# pots-board.net
KiCad netlist of a schematic drawn in EAGLE
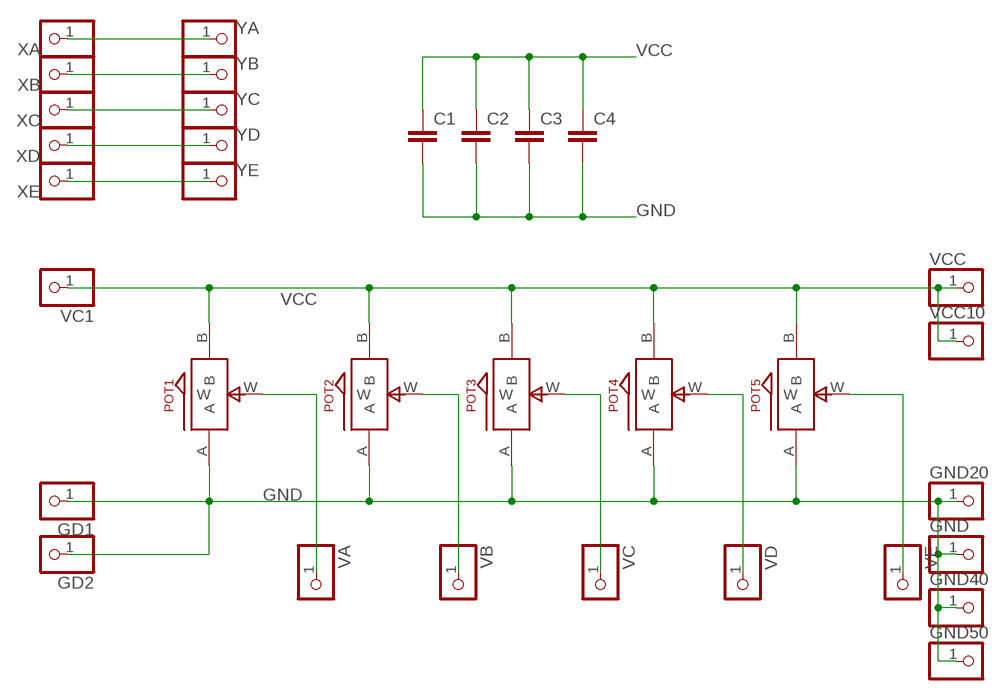
[diagram p0: schematic, sheet 1]

(export (version "E")
  (design (tool "Eeschema 10.0.6"))
  (components
    (comp (ref "C1")
      (value "C-EUC0805")
      (footprint "eagle-import:C0805")
      (libsource (lib "eagle-import") (part "C-EUC0805"))
    )
    (comp (ref "C2")
      (value "C-EUC0805")
      (footprint "eagle-import:C0805")
      (libsource (lib "eagle-import") (part "C-EUC0805"))
    )
    (comp (ref "C3")
      (value "C-EUC0805")
      (footprint "eagle-import:C0805")
      (libsource (lib "eagle-import") (part "C-EUC0805"))
    )
    (comp (ref "C4")
      (value "C-EUC0805")
      (footprint "eagle-import:C0805")
      (libsource (lib "eagle-import") (part "C-EUC0805"))
    )
    (comp (ref "GD1")
      (value "PINHD-1X1")
      (footprint "eagle-import:1X01")
      (libsource (lib "eagle-import") (part "PINHD-1X1"))
    )
    (comp (ref "GD2")
      (value "PINHD-1X1")
      (footprint "eagle-import:1X01")
      (libsource (lib "eagle-import") (part "PINHD-1X1"))
    )
    (comp (ref "GND")
      (value "PINHD-1X1")
      (footprint "eagle-import:1X01")
      (libsource (lib "eagle-import") (part "PINHD-1X1"))
    )
    (comp (ref "GND20")
      (value "PINHD-1X1")
      (footprint "eagle-import:1X01")
      (libsource (lib "eagle-import") (part "PINHD-1X1"))
    )
    (comp (ref "GND40")
      (value "PINHD-1X1")
      (footprint "eagle-import:1X01")
      (libsource (lib "eagle-import") (part "PINHD-1X1"))
    )
    (comp (ref "GND50")
      (value "PINHD-1X1")
      (footprint "eagle-import:1X01")
      (libsource (lib "eagle-import") (part "PINHD-1X1"))
    )
    (comp (ref "POT1")
      (value "ALPS_POT_SMALL")
      (footprint "eagle-import:SMALL_ALPS_POT")
      (libsource (lib "eagle-import") (part "ALPS_POT_SMALL"))
    )
    (comp (ref "POT2")
      (value "ALPS_POT_SMALL")
      (footprint "eagle-import:SMALL_ALPS_POT")
      (libsource (lib "eagle-import") (part "ALPS_POT_SMALL"))
    )
    (comp (ref "POT3")
      (value "ALPS_POT_SMALL")
      (footprint "eagle-import:SMALL_ALPS_POT")
      (libsource (lib "eagle-import") (part "ALPS_POT_SMALL"))
    )
    (comp (ref "POT4")
      (value "ALPS_POT_SMALL")
      (footprint "eagle-import:SMALL_ALPS_POT")
      (libsource (lib "eagle-import") (part "ALPS_POT_SMALL"))
    )
    (comp (ref "POT5")
      (value "ALPS_POT_SMALL")
      (footprint "eagle-import:SMALL_ALPS_POT")
      (libsource (lib "eagle-import") (part "ALPS_POT_SMALL"))
    )
    (comp (ref "VA")
      (value "PINHD-1X1")
      (footprint "eagle-import:1X01")
      (libsource (lib "eagle-import") (part "PINHD-1X1"))
    )
    (comp (ref "VB")
      (value "PINHD-1X1")
      (footprint "eagle-import:1X01")
      (libsource (lib "eagle-import") (part "PINHD-1X1"))
    )
    (comp (ref "VC")
      (value "PINHD-1X1")
      (footprint "eagle-import:1X01")
      (libsource (lib "eagle-import") (part "PINHD-1X1"))
    )
    (comp (ref "VC1")
      (value "PINHD-1X1")
      (footprint "eagle-import:1X01")
      (libsource (lib "eagle-import") (part "PINHD-1X1"))
    )
    (comp (ref "VCC")
      (value "PINHD-1X1")
      (footprint "eagle-import:1X01")
      (libsource (lib "eagle-import") (part "PINHD-1X1"))
    )
    (comp (ref "VCC10")
      (value "PINHD-1X1")
      (footprint "eagle-import:1X01")
      (libsource (lib "eagle-import") (part "PINHD-1X1"))
    )
    (comp (ref "VD")
      (value "PINHD-1X1")
      (footprint "eagle-import:1X01")
      (libsource (lib "eagle-import") (part "PINHD-1X1"))
    )
    (comp (ref "VE")
      (value "PINHD-1X1")
      (footprint "eagle-import:1X01")
      (libsource (lib "eagle-import") (part "PINHD-1X1"))
    )
    (comp (ref "XA")
      (value "PINHD-1X1")
      (footprint "eagle-import:1X01")
      (libsource (lib "eagle-import") (part "PINHD-1X1"))
    )
    (comp (ref "XB")
      (value "PINHD-1X1")
      (footprint "eagle-import:1X01")
      (libsource (lib "eagle-import") (part "PINHD-1X1"))
    )
    (comp (ref "XC")
      (value "PINHD-1X1")
      (footprint "eagle-import:1X01")
      (libsource (lib "eagle-import") (part "PINHD-1X1"))
    )
    (comp (ref "XD")
      (value "PINHD-1X1")
      (footprint "eagle-import:1X01")
      (libsource (lib "eagle-import") (part "PINHD-1X1"))
    )
    (comp (ref "XE")
      (value "PINHD-1X1")
      (footprint "eagle-import:1X01")
      (libsource (lib "eagle-import") (part "PINHD-1X1"))
    )
    (comp (ref "YA")
      (value "PINHD-1X1")
      (footprint "eagle-import:1X01")
      (libsource (lib "eagle-import") (part "PINHD-1X1"))
    )
    (comp (ref "YB")
      (value "PINHD-1X1")
      (footprint "eagle-import:1X01")
      (libsource (lib "eagle-import") (part "PINHD-1X1"))
    )
    (comp (ref "YC")
      (value "PINHD-1X1")
      (footprint "eagle-import:1X01")
      (libsource (lib "eagle-import") (part "PINHD-1X1"))
    )
    (comp (ref "YD")
      (value "PINHD-1X1")
      (footprint "eagle-import:1X01")
      (libsource (lib "eagle-import") (part "PINHD-1X1"))
    )
    (comp (ref "YE")
      (value "PINHD-1X1")
      (footprint "eagle-import:1X01")
      (libsource (lib "eagle-import") (part "PINHD-1X1"))
    )
  )
  (nets
    (net (code "1") (name "/GND") (class "Default")
      (node (ref "C1") (pin "2") (pinfunction "2_2") (pintype "passive"))
      (node (ref "C2") (pin "2") (pinfunction "2_2") (pintype "passive"))
      (node (ref "C3") (pin "2") (pinfunction "2_2") (pintype "passive"))
      (node (ref "C4") (pin "2") (pinfunction "2_2") (pintype "passive"))
      (node (ref "GD1") (pin "1") (pinfunction "1_1") (pintype "passive"))
      (node (ref "GD2") (pin "1") (pinfunction "1_1") (pintype "passive"))
      (node (ref "GND") (pin "1") (pinfunction "1_1") (pintype "passive"))
      (node (ref "GND20") (pin "1") (pinfunction "1_1") (pintype "passive"))
      (node (ref "GND40") (pin "1") (pinfunction "1_1") (pintype "passive"))
      (node (ref "GND50") (pin "1") (pinfunction "1_1") (pintype "passive"))
      (node (ref "POT1") (pin "A") (pinfunction "A_A") (pintype "bidirectional"))
      (node (ref "POT2") (pin "A") (pinfunction "A_A") (pintype "bidirectional"))
      (node (ref "POT3") (pin "A") (pinfunction "A_A") (pintype "bidirectional"))
      (node (ref "POT4") (pin "A") (pinfunction "A_A") (pintype "bidirectional"))
      (node (ref "POT5") (pin "A") (pinfunction "A_A") (pintype "bidirectional"))
    )
    (net (code "2") (name "/VCC") (class "Default")
      (node (ref "C1") (pin "1") (pinfunction "1_1") (pintype "passive"))
      (node (ref "C2") (pin "1") (pinfunction "1_1") (pintype "passive"))
      (node (ref "C3") (pin "1") (pinfunction "1_1") (pintype "passive"))
      (node (ref "C4") (pin "1") (pinfunction "1_1") (pintype "passive"))
      (node (ref "POT1") (pin "B") (pinfunction "B_B") (pintype "bidirectional"))
      (node (ref "POT2") (pin "B") (pinfunction "B_B") (pintype "bidirectional"))
      (node (ref "POT3") (pin "B") (pinfunction "B_B") (pintype "bidirectional"))
      (node (ref "POT4") (pin "B") (pinfunction "B_B") (pintype "bidirectional"))
      (node (ref "POT5") (pin "B") (pinfunction "B_B") (pintype "bidirectional"))
      (node (ref "VC1") (pin "1") (pinfunction "1_1") (pintype "passive"))
      (node (ref "VCC") (pin "1") (pinfunction "1_1") (pintype "passive"))
      (node (ref "VCC10") (pin "1") (pinfunction "1_1") (pintype "passive"))
    )
    (net (code "3") (name "Net-(POT1-PadW)") (class "Default")
      (node (ref "POT1") (pin "W") (pinfunction "W_W") (pintype "bidirectional"))
      (node (ref "VA") (pin "1") (pinfunction "1_1") (pintype "passive"))
    )
    (net (code "4") (name "Net-(POT2-PadW)") (class "Default")
      (node (ref "POT2") (pin "W") (pinfunction "W_W") (pintype "bidirectional"))
      (node (ref "VB") (pin "1") (pinfunction "1_1") (pintype "passive"))
    )
    (net (code "5") (name "Net-(POT3-PadW)") (class "Default")
      (node (ref "POT3") (pin "W") (pinfunction "W_W") (pintype "bidirectional"))
      (node (ref "VC") (pin "1") (pinfunction "1_1") (pintype "passive"))
    )
    (net (code "6") (name "Net-(POT4-PadW)") (class "Default")
      (node (ref "POT4") (pin "W") (pinfunction "W_W") (pintype "bidirectional"))
      (node (ref "VD") (pin "1") (pinfunction "1_1") (pintype "passive"))
    )
    (net (code "7") (name "Net-(POT5-PadW)") (class "Default")
      (node (ref "POT5") (pin "W") (pinfunction "W_W") (pintype "bidirectional"))
      (node (ref "VE") (pin "1") (pinfunction "1_1") (pintype "passive"))
    )
    (net (code "8") (name "Net-(XA-Pad1)") (class "Default")
      (node (ref "XA") (pin "1") (pinfunction "1_1") (pintype "passive"))
      (node (ref "YA") (pin "1") (pinfunction "1_1") (pintype "passive"))
    )
    (net (code "9") (name "Net-(XB-Pad1)") (class "Default")
      (node (ref "XB") (pin "1") (pinfunction "1_1") (pintype "passive"))
      (node (ref "YB") (pin "1") (pinfunction "1_1") (pintype "passive"))
    )
    (net (code "10") (name "Net-(XC-Pad1)") (class "Default")
      (node (ref "XC") (pin "1") (pinfunction "1_1") (pintype "passive"))
      (node (ref "YC") (pin "1") (pinfunction "1_1") (pintype "passive"))
    )
    (net (code "11") (name "Net-(XD-Pad1)") (class "Default")
      (node (ref "XD") (pin "1") (pinfunction "1_1") (pintype "passive"))
      (node (ref "YD") (pin "1") (pinfunction "1_1") (pintype "passive"))
    )
    (net (code "12") (name "Net-(XE-Pad1)") (class "Default")
      (node (ref "XE") (pin "1") (pinfunction "1_1") (pintype "passive"))
      (node (ref "YE") (pin "1") (pinfunction "1_1") (pintype "passive"))
    )
  )
)
